# Resolver.net
KiCad netlist of a schematic drawn in Altium Designer
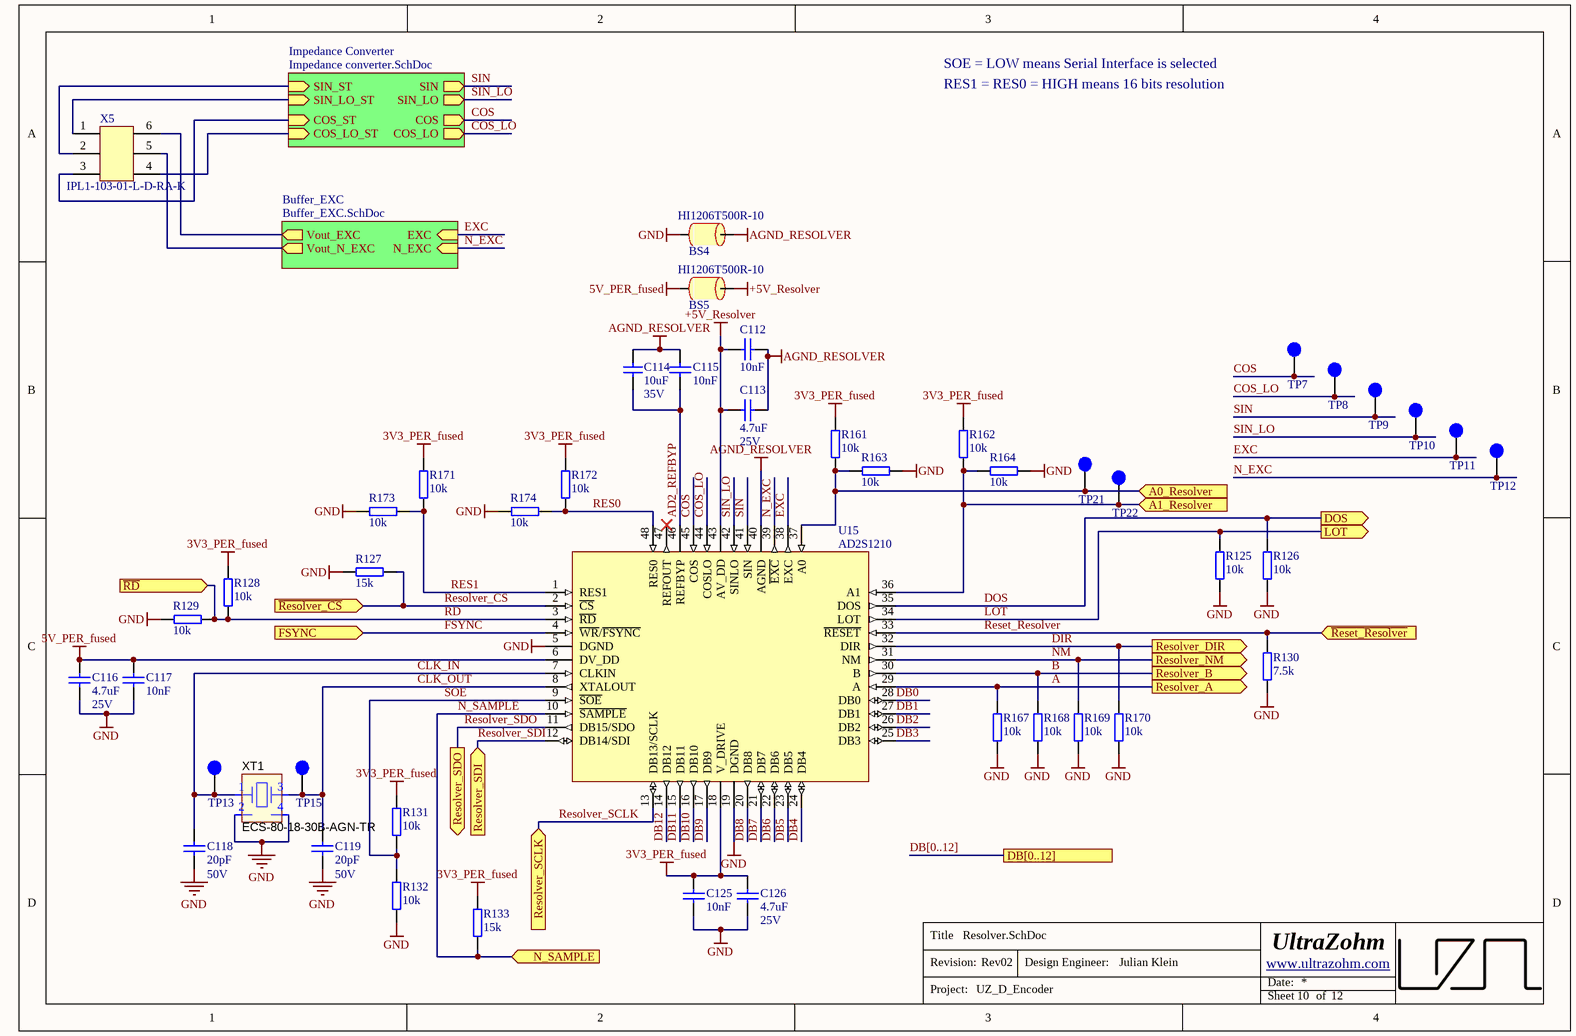
[diagram p0: Resolver.SchDoc]

(export (version "E")
  (design (tool "Eeschema 10.0.6"))
  (components
    (comp (ref "BS4")
      (value "HI1206T500R-10")
      (footprint "RES_1206")
      (description "Ferrite bead 6A")
      (fields (field (name "MF") "Laird"))
      (libsource (lib "Componentes_SOC") (part "Bead"))
    )
    (comp (ref "BS5")
      (value "HI1206T500R-10")
      (footprint "RES_1206")
      (description "Ferrite bead 6A")
      (fields (field (name "MF") "Laird"))
      (libsource (lib "Componentes_SOC") (part "Bead"))
    )
    (comp (ref "C112")
      (value "10nF")
      (footprint "CAPC1608X07N")
      (fields (field (name "MF") "Würth") (field (name "MPN") "885012206065") (field (name "VOLTAGE") "25V"))
      (libsource (lib "UltraZohm_ADC") (part "Cap_0603"))
    )
    (comp (ref "C113")
      (value "4.7uF")
      (footprint "CAPC1608X07N")
      (fields (field (name "VOLTAGE") "25V"))
      (libsource (lib "UltraZohm_ADC") (part "Cap_0603"))
    )
    (comp (ref "C114")
      (value "10uF")
      (footprint "C_1206")
      (description "Capacitor 1206")
      (fields
        (field (name "TOLERANCE") "10%")
        (field (name "MF") "Murata Electronics")
        (field (name "VOLTAGE") "35V")
        (field (name "CREATED") "2018_06_25_AGeiger")
      )
      (libsource (lib "UltraZohm_ADC") (part "C_1206"))
    )
    (comp (ref "C115")
      (value "10nF")
      (footprint "CAPC1608X07N")
      (fields (field (name "MF") "Würth") (field (name "MPN") "885012206065") (field (name "VOLTAGE") "25V"))
      (libsource (lib "UltraZohm_ADC") (part "Cap_0603"))
    )
    (comp (ref "C116")
      (value "4.7uF")
      (footprint "CAPC1608X07N")
      (fields (field (name "VOLTAGE") "25V"))
      (libsource (lib "UltraZohm_ADC") (part "Cap_0603"))
    )
    (comp (ref "C117")
      (value "10nF")
      (footprint "CAPC1608X07N")
      (fields (field (name "MF") "Würth") (field (name "MPN") "885012206065") (field (name "VOLTAGE") "25V"))
      (libsource (lib "UltraZohm_ADC") (part "Cap_0603"))
    )
    (comp (ref "C118")
      (value "20pF")
      (footprint "CAPC1608X07N")
      (fields (field (name "VOLTAGE") "50V"))
      (libsource (lib "UltraZohm_ADC") (part "Cap_0603"))
    )
    (comp (ref "C119")
      (value "20pF")
      (footprint "CAPC1608X07N")
      (fields (field (name "VOLTAGE") "50V"))
      (libsource (lib "UltraZohm_ADC") (part "Cap_0603"))
    )
    (comp (ref "C125")
      (value "10nF")
      (footprint "CAPC1608X07N")
      (fields (field (name "MF") "Würth") (field (name "MPN") "885012206065") (field (name "VOLTAGE") "25V"))
      (libsource (lib "UltraZohm_ADC") (part "Cap_0603"))
    )
    (comp (ref "C126")
      (value "4.7uF")
      (footprint "CAPC1608X07N")
      (fields (field (name "VOLTAGE") "25V"))
      (libsource (lib "UltraZohm_ADC") (part "Cap_0603"))
    )
    (comp (ref "R125")
      (value "10k")
      (footprint "RESC1608X06N")
      (fields (field (name "MF") "Vishay") (field (name "MPN") "CRCW06030000Z0EAC"))
      (libsource (lib "UltraZohm_ADC") (part "R_0603"))
    )
    (comp (ref "R126")
      (value "10k")
      (footprint "RESC1608X06N")
      (fields (field (name "MF") "Vishay") (field (name "MPN") "CRCW06030000Z0EAC"))
      (libsource (lib "UltraZohm_ADC") (part "R_0603"))
    )
    (comp (ref "R127")
      (value "15k")
      (footprint "RESC1608X06N")
      (fields (field (name "MF") "Vishay") (field (name "MPN") "CRCW06030000Z0EAC"))
      (libsource (lib "UltraZohm_ADC") (part "R_0603"))
    )
    (comp (ref "R128")
      (value "10k")
      (footprint "RESC1608X06N")
      (fields (field (name "MF") "Vishay") (field (name "MPN") "CRCW06030000Z0EAC"))
      (libsource (lib "UltraZohm_ADC") (part "R_0603"))
    )
    (comp (ref "R129")
      (value "10k")
      (footprint "RESC1608X06N")
      (fields (field (name "MF") "Vishay") (field (name "MPN") "CRCW06030000Z0EAC"))
      (libsource (lib "UltraZohm_ADC") (part "R_0603"))
    )
    (comp (ref "R130")
      (value "7.5k")
      (footprint "RESC1608X06N")
      (libsource (lib "UltraZohm_ADC") (part "R_0603"))
    )
    (comp (ref "R131")
      (value "10k")
      (footprint "RESC1608X06N")
      (fields (field (name "MF") "Vishay") (field (name "MPN") "CRCW06030000Z0EAC"))
      (libsource (lib "UltraZohm_ADC") (part "R_0603"))
    )
    (comp (ref "R132")
      (value "10k")
      (footprint "RESC1608X06N")
      (fields (field (name "MF") "Vishay") (field (name "MPN") "CRCW06030000Z0EAC"))
      (libsource (lib "UltraZohm_ADC") (part "R_0603"))
    )
    (comp (ref "R133")
      (value "15k")
      (footprint "RESC1608X06N")
      (fields (field (name "MF") "Vishay") (field (name "MPN") "CRCW06030000Z0EAC"))
      (libsource (lib "UltraZohm_ADC") (part "R_0603"))
    )
    (comp (ref "R161")
      (value "10k")
      (footprint "RESC1608X06N")
      (fields (field (name "MF") "Vishay") (field (name "MPN") "CRCW06030000Z0EAC"))
      (libsource (lib "UltraZohm_ADC") (part "R_0603"))
    )
    (comp (ref "R162")
      (value "10k")
      (footprint "RESC1608X06N")
      (fields (field (name "MF") "Vishay") (field (name "MPN") "CRCW06030000Z0EAC"))
      (libsource (lib "UltraZohm_ADC") (part "R_0603"))
    )
    (comp (ref "R163")
      (value "10k")
      (footprint "RESC1608X06N")
      (fields (field (name "MF") "Vishay") (field (name "MPN") "CRCW06030000Z0EAC"))
      (libsource (lib "UltraZohm_ADC") (part "R_0603"))
    )
    (comp (ref "R164")
      (value "10k")
      (footprint "RESC1608X06N")
      (fields (field (name "MF") "Vishay") (field (name "MPN") "CRCW06030000Z0EAC"))
      (libsource (lib "UltraZohm_ADC") (part "R_0603"))
    )
    (comp (ref "R167")
      (value "10k")
      (footprint "RESC1608X06N")
      (fields (field (name "MF") "Vishay") (field (name "MPN") "CRCW06030000Z0EAC"))
      (libsource (lib "UltraZohm_ADC") (part "R_0603"))
    )
    (comp (ref "R168")
      (value "10k")
      (footprint "RESC1608X06N")
      (fields (field (name "MF") "Vishay") (field (name "MPN") "CRCW06030000Z0EAC"))
      (libsource (lib "UltraZohm_ADC") (part "R_0603"))
    )
    (comp (ref "R169")
      (value "10k")
      (footprint "RESC1608X06N")
      (fields (field (name "MF") "Vishay") (field (name "MPN") "CRCW06030000Z0EAC"))
      (libsource (lib "UltraZohm_ADC") (part "R_0603"))
    )
    (comp (ref "R170")
      (value "10k")
      (footprint "RESC1608X06N")
      (fields (field (name "MF") "Vishay") (field (name "MPN") "CRCW06030000Z0EAC"))
      (libsource (lib "UltraZohm_ADC") (part "R_0603"))
    )
    (comp (ref "R171")
      (value "10k")
      (footprint "RESC1608X06N")
      (fields (field (name "MF") "Vishay") (field (name "MPN") "CRCW06030000Z0EAC"))
      (libsource (lib "UltraZohm_ADC") (part "R_0603"))
    )
    (comp (ref "R172")
      (value "10k")
      (footprint "RESC1608X06N")
      (fields (field (name "MF") "Vishay") (field (name "MPN") "CRCW06030000Z0EAC"))
      (libsource (lib "UltraZohm_ADC") (part "R_0603"))
    )
    (comp (ref "R173")
      (value "10k")
      (footprint "RESC1608X06N")
      (fields (field (name "MF") "Vishay") (field (name "MPN") "CRCW06030000Z0EAC"))
      (libsource (lib "UltraZohm_ADC") (part "R_0603"))
    )
    (comp (ref "R174")
      (value "10k")
      (footprint "RESC1608X06N")
      (fields (field (name "MF") "Vishay") (field (name "MPN") "CRCW06030000Z0EAC"))
      (libsource (lib "UltraZohm_ADC") (part "R_0603"))
    )
    (comp (ref "TP7")
      (value "VCC")
      (footprint "TP_1mm")
      (description "Testpoint 1mm")
      (fields (field (name "CREATED") "2018_06_25_AGeiger"))
      (libsource (lib "UltraZOhm_CarrierBoard") (part "TP_1mm"))
    )
    (comp (ref "TP8")
      (value "VCC")
      (footprint "TP_1mm")
      (description "Testpoint 1mm")
      (fields (field (name "CREATED") "2018_06_25_AGeiger"))
      (libsource (lib "UltraZOhm_CarrierBoard") (part "TP_1mm"))
    )
    (comp (ref "TP9")
      (value "VCC")
      (footprint "TP_1mm")
      (description "Testpoint 1mm")
      (fields (field (name "CREATED") "2018_06_25_AGeiger"))
      (libsource (lib "UltraZOhm_CarrierBoard") (part "TP_1mm"))
    )
    (comp (ref "TP10")
      (value "VCC")
      (footprint "TP_1mm")
      (description "Testpoint 1mm")
      (fields (field (name "CREATED") "2018_06_25_AGeiger"))
      (libsource (lib "UltraZOhm_CarrierBoard") (part "TP_1mm"))
    )
    (comp (ref "TP11")
      (value "VCC")
      (footprint "TP_1mm")
      (description "Testpoint 1mm")
      (fields (field (name "CREATED") "2018_06_25_AGeiger"))
      (libsource (lib "UltraZOhm_CarrierBoard") (part "TP_1mm"))
    )
    (comp (ref "TP12")
      (value "VCC")
      (footprint "TP_1mm")
      (description "Testpoint 1mm")
      (fields (field (name "CREATED") "2018_06_25_AGeiger"))
      (libsource (lib "UltraZOhm_CarrierBoard") (part "TP_1mm"))
    )
    (comp (ref "TP13")
      (value "VCC")
      (footprint "TP_1mm")
      (description "Testpoint 1mm")
      (fields (field (name "CREATED") "2018_06_25_AGeiger"))
      (libsource (lib "UltraZOhm_CarrierBoard") (part "TP_1mm"))
    )
    (comp (ref "TP15")
      (value "VCC")
      (footprint "TP_1mm")
      (description "Testpoint 1mm")
      (fields (field (name "CREATED") "2018_06_25_AGeiger"))
      (libsource (lib "UltraZOhm_CarrierBoard") (part "TP_1mm"))
    )
    (comp (ref "TP21")
      (value "VCC")
      (footprint "TP_1mm")
      (description "Testpoint 1mm")
      (fields (field (name "CREATED") "2018_06_25_AGeiger"))
      (libsource (lib "UltraZOhm_CarrierBoard") (part "TP_1mm"))
    )
    (comp (ref "TP22")
      (value "VCC")
      (footprint "TP_1mm")
      (description "Testpoint 1mm")
      (fields (field (name "CREATED") "2018_06_25_AGeiger"))
      (libsource (lib "UltraZOhm_CarrierBoard") (part "TP_1mm"))
    )
    (comp (ref "U15")
      (value "AD2S1210")
      (footprint "LQFP-48_L")
      (description "Variable Resolution, 10-Bit to 16-Bit R/D Converter with Reference Oscillator")
      (fields
        (field (name "MF") "Analog Devices")
        (field (name "MPN") "AD2S1210WDSTZRL7")
        (field (name "CREATED") "2019_04_20_AGeiger")
      )
      (libsource (lib "AD_AD2S1210") (part "AD2S1210"))
    )
    (comp (ref "X5")
      (value "IPL1-103-01-L-D-RA-K")
      (footprint "Conector 3x2 TH Horizontal")
      (description "CONN HEADER R/A 6 POS 2.54MM Through Hole")
      (fields (field (name "MF") "Samtec"))
      (libsource (lib "Componentes_SOC") (part "Conector 3x2 Horizontal"))
    )
    (comp (ref "XT1")
      (value "ECS-80-18-30B-AGN-TR")
      (footprint "CRYSTALOSC")
      (description "CRYSTAL 8MHZ 18PF SMD")
      (fields (field (name "MF") "ECS"))
      (libsource (lib "Componentes_SOC") (part "Crystal_8MHz"))
    )
  )
  (nets
    (net (code "1") (name "+5V_Resolver") (class "Default")
      (node (ref "BS5") (pin "1") (pintype "passive"))
      (node (ref "C112") (pin "1") (pinfunction "1_1") (pintype "passive"))
      (node (ref "C113") (pin "1") (pinfunction "1_1") (pintype "passive"))
      (node (ref "U15") (pin "43") (pinfunction "AV_DD_43") (pintype "power_in"))
    )
    (net (code "2") (name "/A") (class "Default")
      (node (ref "R167") (pin "2") (pintype "passive"))
      (node (ref "U15") (pin "29") (pinfunction "A_29") (pintype "input"))
    )
    (net (code "3") (name "/A0_Resolver") (class "Default")
      (node (ref "R161") (pin "1") (pintype "passive"))
      (node (ref "R163") (pin "2") (pintype "passive"))
      (node (ref "TP21") (pin "1") (pintype "passive"))
      (node (ref "U15") (pin "37") (pinfunction "A0_37") (pintype "input"))
    )
    (net (code "4") (name "/A1_Resolver") (class "Default")
      (node (ref "R162") (pin "1") (pintype "passive"))
      (node (ref "R164") (pin "2") (pintype "passive"))
      (node (ref "TP22") (pin "1") (pintype "passive"))
      (node (ref "U15") (pin "36") (pinfunction "A1_36") (pintype "input"))
    )
    (net (code "5") (name "/AD2_REFBYP") (class "Default")
      (node (ref "C114") (pin "1") (pinfunction "1_1") (pintype "passive"))
      (node (ref "C115") (pin "1") (pinfunction "1_1") (pintype "passive"))
      (node (ref "U15") (pin "46") (pinfunction "REFBYP_46") (pintype "passive"))
    )
    (net (code "6") (name "/B") (class "Default")
      (node (ref "R168") (pin "2") (pintype "passive"))
      (node (ref "U15") (pin "30") (pinfunction "B_30") (pintype "output"))
    )
    (net (code "7") (name "/CLK_IN") (class "Default")
      (node (ref "C118") (pin "1") (pinfunction "1_1") (pintype "passive"))
      (node (ref "TP13") (pin "1") (pintype "passive"))
      (node (ref "U15") (pin "7") (pinfunction "CLKIN_7") (pintype "input"))
      (node (ref "XT1") (pin "1") (pinfunction "IN_1") (pintype "passive"))
    )
    (net (code "8") (name "/CLK_OUT") (class "Default")
      (node (ref "C119") (pin "1") (pinfunction "1_1") (pintype "passive"))
      (node (ref "TP15") (pin "1") (pintype "passive"))
      (node (ref "U15") (pin "8") (pinfunction "XTALOUT_8") (pintype "output"))
      (node (ref "XT1") (pin "3") (pinfunction "OUT_3") (pintype "passive"))
    )
    (net (code "9") (name "/COS") (class "Default")
      (node (ref "TP7") (pin "1") (pintype "passive"))
      (node (ref "U15") (pin "45") (pinfunction "COS_45") (pintype "input"))
    )
    (net (code "10") (name "/COS_LO") (class "Default")
      (node (ref "TP8") (pin "1") (pintype "passive"))
      (node (ref "U15") (pin "44") (pinfunction "COSLO_44") (pintype "input"))
    )
    (net (code "11") (name "/COS_LO_ST") (class "Default") (node (ref "X5") (pin "4") (pintype "passive")))
    (net (code "12") (name "/COS_ST") (class "Default") (node (ref "X5") (pin "3") (pintype "passive")))
    (net (code "13") (name "/DB0") (class "Default")
      (node (ref "U15") (pin "28") (pinfunction "DB0_28") (pintype "bidirectional"))
    )
    (net (code "14") (name "/DB1") (class "Default")
      (node (ref "U15") (pin "27") (pinfunction "DB1_27") (pintype "bidirectional"))
    )
    (net (code "15") (name "/DB2") (class "Default")
      (node (ref "U15") (pin "26") (pinfunction "DB2_26") (pintype "bidirectional"))
    )
    (net (code "16") (name "/DB3") (class "Default")
      (node (ref "U15") (pin "25") (pinfunction "DB3_25") (pintype "bidirectional"))
    )
    (net (code "17") (name "/DB4") (class "Default")
      (node (ref "U15") (pin "24") (pinfunction "DB4_24") (pintype "bidirectional"))
    )
    (net (code "18") (name "/DB5") (class "Default")
      (node (ref "U15") (pin "23") (pinfunction "DB5_23") (pintype "bidirectional"))
    )
    (net (code "19") (name "/DB6") (class "Default")
      (node (ref "U15") (pin "22") (pinfunction "DB6_22") (pintype "bidirectional"))
    )
    (net (code "20") (name "/DB7") (class "Default")
      (node (ref "U15") (pin "21") (pinfunction "DB7_21") (pintype "bidirectional"))
    )
    (net (code "21") (name "/DB8") (class "Default")
      (node (ref "U15") (pin "20") (pinfunction "DB8_20") (pintype "output"))
    )
    (net (code "22") (name "/DB9") (class "Default")
      (node (ref "U15") (pin "17") (pinfunction "DB9_17") (pintype "output"))
    )
    (net (code "23") (name "/DB10") (class "Default")
      (node (ref "U15") (pin "16") (pinfunction "DB10_16") (pintype "output"))
    )
    (net (code "24") (name "/DB11") (class "Default")
      (node (ref "U15") (pin "15") (pinfunction "DB11_15") (pintype "output"))
    )
    (net (code "25") (name "/DB12") (class "Default")
      (node (ref "U15") (pin "14") (pinfunction "DB12_14") (pintype "output"))
    )
    (net (code "27") (name "/DIR") (class "Default")
      (node (ref "R170") (pin "2") (pintype "passive"))
      (node (ref "U15") (pin "32") (pinfunction "DIR_32") (pintype "output"))
    )
    (net (code "28") (name "/DOS") (class "Default")
      (node (ref "R126") (pin "2") (pintype "passive"))
      (node (ref "U15") (pin "35") (pinfunction "DOS_35") (pintype "output"))
    )
    (net (code "29") (name "/EXC") (class "Default")
      (node (ref "TP11") (pin "1") (pintype "passive"))
      (node (ref "U15") (pin "38") (pinfunction "EXC_38") (pintype "output"))
    )
    (net (code "30") (name "/FSYNC") (class "Default")
      (node (ref "U15") (pin "4") (pinfunction "~{WR}/~{FSYNC}_4") (pintype "input"))
    )
    (net (code "31") (name "/LOT") (class "Default")
      (node (ref "R125") (pin "2") (pintype "passive"))
      (node (ref "U15") (pin "34") (pinfunction "LOT_34") (pintype "output"))
    )
    (net (code "32") (name "/NM") (class "Default")
      (node (ref "R169") (pin "2") (pintype "passive"))
      (node (ref "U15") (pin "31") (pinfunction "NM_31") (pintype "output"))
    )
    (net (code "33") (name "/N_EXC") (class "Default")
      (node (ref "TP12") (pin "1") (pintype "passive"))
      (node (ref "U15") (pin "39") (pinfunction "~{EXC}_39") (pintype "output"))
    )
    (net (code "34") (name "/N_SAMPLE") (class "Default")
      (node (ref "R133") (pin "1") (pintype "passive"))
      (node (ref "U15") (pin "10") (pinfunction "~{SAMPLE}_10") (pintype "input"))
    )
    (net (code "35") (name "/RES0") (class "Default")
      (node (ref "R172") (pin "1") (pintype "passive"))
      (node (ref "R174") (pin "2") (pintype "passive"))
      (node (ref "U15") (pin "48") (pinfunction "RES0_48") (pintype "input"))
    )
    (net (code "36") (name "/RES1") (class "Default")
      (node (ref "R171") (pin "1") (pintype "passive"))
      (node (ref "R173") (pin "2") (pintype "passive"))
      (node (ref "U15") (pin "1") (pinfunction "RES1_1") (pintype "input"))
    )
    (net (code "37") (name "/Reset_Resolver") (class "Default")
      (node (ref "R130") (pin "1") (pintype "passive"))
      (node (ref "U15") (pin "33") (pinfunction "~{RESET}_33") (pintype "input"))
    )
    (net (code "38") (name "/Resolver_CS") (class "Default")
      (node (ref "R127") (pin "1") (pintype "passive"))
      (node (ref "U15") (pin "2") (pinfunction "~{CS}_2") (pintype "input"))
    )
    (net (code "39") (name "/Resolver_SCLK") (class "Default")
      (node (ref "U15") (pin "13") (pinfunction "DB13/SCLK_13") (pintype "bidirectional"))
    )
    (net (code "40") (name "/Resolver_SDI") (class "Default")
      (node (ref "U15") (pin "12") (pinfunction "DB14/SDI_12") (pintype "bidirectional"))
    )
    (net (code "41") (name "/Resolver_SDO") (class "Default")
      (node (ref "U15") (pin "11") (pinfunction "DB15/SDO_11") (pintype "output"))
    )
    (net (code "42") (name "/SIN") (class "Default")
      (node (ref "TP9") (pin "1") (pintype "passive"))
      (node (ref "U15") (pin "41") (pinfunction "SIN_41") (pintype "input"))
    )
    (net (code "43") (name "/SIN_LO") (class "Default")
      (node (ref "TP10") (pin "1") (pintype "passive"))
      (node (ref "U15") (pin "42") (pinfunction "SINLO_42") (pintype "input"))
    )
    (net (code "44") (name "/SIN_LO_ST") (class "Default") (node (ref "X5") (pin "1") (pintype "passive")))
    (net (code "45") (name "/SIN_ST") (class "Default") (node (ref "X5") (pin "2") (pintype "passive")))
    (net (code "46") (name "/Vout_EXC") (class "Default") (node (ref "X5") (pin "6") (pintype "passive")))
    (net (code "47") (name "/Vout_N_EXC") (class "Default") (node (ref "X5") (pin "5") (pintype "passive")))
    (net (code "48") (name "/~{RD}") (class "Default")
      (node (ref "R128") (pin "1") (pintype "passive"))
      (node (ref "R129") (pin "2") (pintype "passive"))
      (node (ref "U15") (pin "3") (pinfunction "~{RD}_3") (pintype "input"))
    )
    (net (code "49") (name "/~{SOE}") (class "Default")
      (node (ref "R131") (pin "1") (pintype "passive"))
      (node (ref "R132") (pin "2") (pintype "passive"))
      (node (ref "U15") (pin "9") (pinfunction "~{SOE}_9") (pintype "input"))
    )
    (net (code "50") (name "3V3_PER_fused") (class "Default")
      (node (ref "C125") (pin "2") (pinfunction "2_2") (pintype "passive"))
      (node (ref "C126") (pin "2") (pinfunction "2_2") (pintype "passive"))
      (node (ref "R128") (pin "2") (pintype "passive"))
      (node (ref "R131") (pin "2") (pintype "passive"))
      (node (ref "R133") (pin "2") (pintype "passive"))
      (node (ref "R161") (pin "2") (pintype "passive"))
      (node (ref "R162") (pin "2") (pintype "passive"))
      (node (ref "R171") (pin "2") (pintype "passive"))
      (node (ref "R172") (pin "2") (pintype "passive"))
      (node (ref "U15") (pin "18") (pinfunction "V_DRIVE_18") (pintype "power_in"))
    )
    (net (code "51") (name "5V_PER_fused") (class "Default")
      (node (ref "BS5") (pin "2") (pintype "passive"))
      (node (ref "C116") (pin "2") (pinfunction "2_2") (pintype "passive"))
      (node (ref "C117") (pin "2") (pinfunction "2_2") (pintype "passive"))
      (node (ref "U15") (pin "6") (pinfunction "DV_DD_6") (pintype "power_in"))
    )
    (net (code "52") (name "AGND_RESOLVER") (class "Default")
      (node (ref "BS4") (pin "1") (pintype "passive"))
      (node (ref "C112") (pin "2") (pinfunction "2_2") (pintype "passive"))
      (node (ref "C113") (pin "2") (pinfunction "2_2") (pintype "passive"))
      (node (ref "C114") (pin "2") (pinfunction "2_2") (pintype "passive"))
      (node (ref "C115") (pin "2") (pinfunction "2_2") (pintype "passive"))
      (node (ref "U15") (pin "40") (pinfunction "AGND_40") (pintype "power_in"))
    )
    (net (code "53") (name "GND") (class "Default")
      (node (ref "BS4") (pin "2") (pintype "passive"))
      (node (ref "C116") (pin "1") (pinfunction "1_1") (pintype "passive"))
      (node (ref "C117") (pin "1") (pinfunction "1_1") (pintype "passive"))
      (node (ref "C118") (pin "2") (pinfunction "2_2") (pintype "passive"))
      (node (ref "C119") (pin "2") (pinfunction "2_2") (pintype "passive"))
      (node (ref "C125") (pin "1") (pinfunction "1_1") (pintype "passive"))
      (node (ref "C126") (pin "1") (pinfunction "1_1") (pintype "passive"))
      (node (ref "R125") (pin "1") (pintype "passive"))
      (node (ref "R126") (pin "1") (pintype "passive"))
      (node (ref "R127") (pin "2") (pintype "passive"))
      (node (ref "R129") (pin "1") (pintype "passive"))
      (node (ref "R130") (pin "2") (pintype "passive"))
      (node (ref "R132") (pin "1") (pintype "passive"))
      (node (ref "R163") (pin "1") (pintype "passive"))
      (node (ref "R164") (pin "1") (pintype "passive"))
      (node (ref "R167") (pin "1") (pintype "passive"))
      (node (ref "R168") (pin "1") (pintype "passive"))
      (node (ref "R169") (pin "1") (pintype "passive"))
      (node (ref "R170") (pin "1") (pintype "passive"))
      (node (ref "R173") (pin "1") (pintype "passive"))
      (node (ref "R174") (pin "1") (pintype "passive"))
      (node (ref "U15") (pin "19") (pinfunction "DGND_19") (pintype "power_in"))
      (node (ref "U15") (pin "5") (pinfunction "DGND_5") (pintype "power_in"))
      (node (ref "XT1") (pin "2") (pinfunction "GND_2") (pintype "passive"))
      (node (ref "XT1") (pin "4") (pinfunction "GND_4") (pintype "passive"))
    )
    (net (code "54") (name "unconnected-(U15-REFOUT-Pad47)") (class "Default")
      (node (ref "U15") (pin "47") (pinfunction "REFOUT_47") (pintype "output+no_connect"))
    )
  )
)
